# T15_PRI_SYS_V1_4.net
KiCad netlist of a schematic drawn in EAGLE
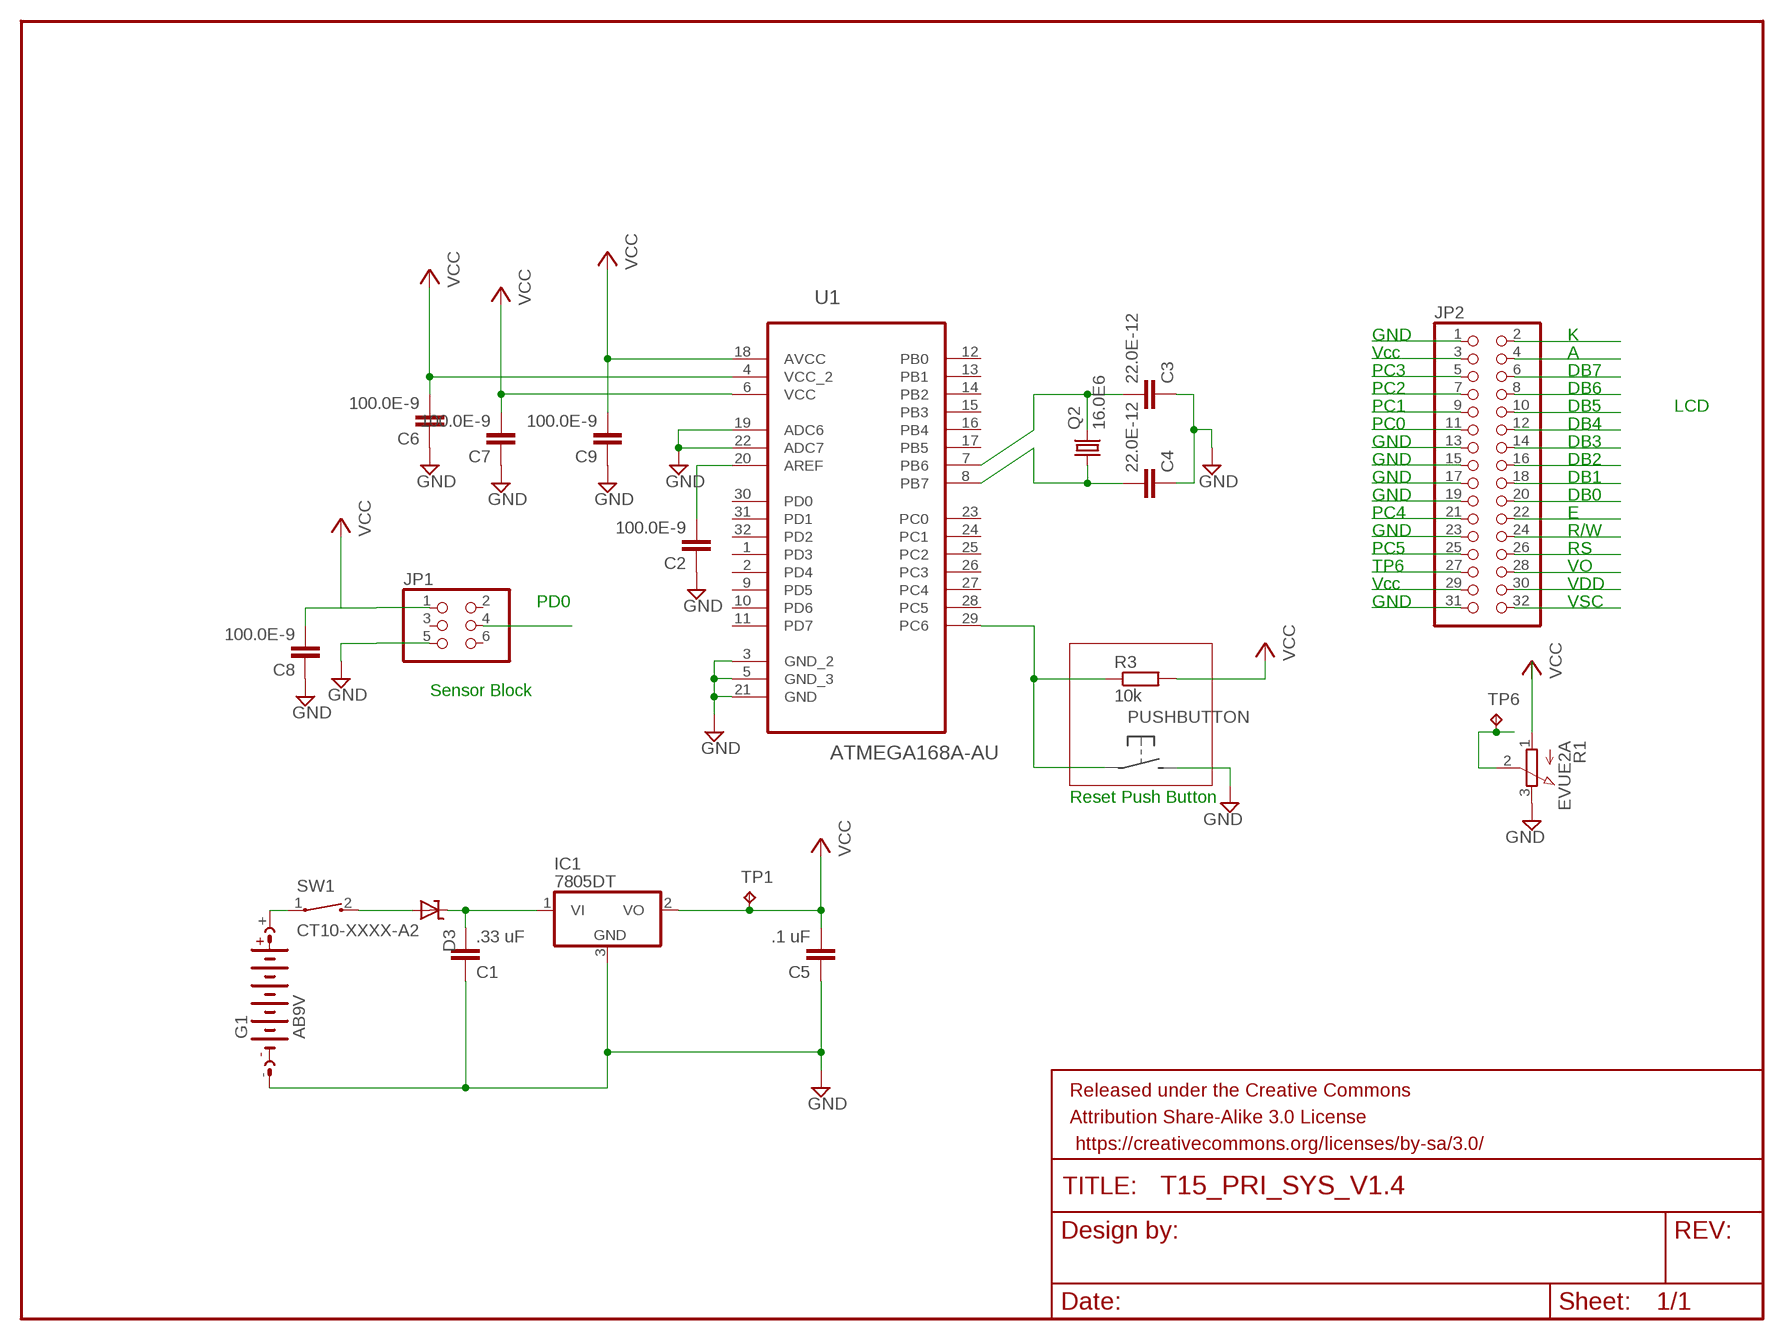
[diagram p0: schematic, sheet 1]

(export (version "E")
  (design (tool "Eeschema 10.0.6"))
  (components
    (comp (ref "C1")
      (value ".33 uF")
      (footprint "eagle-import:C025-024X044")
      (libsource (lib "eagle-import") (part "C-EU025-024X044"))
    )
    (comp (ref "C2")
      (value "100.0E-9")
      (footprint "eagle-import:C025-024X044")
      (libsource (lib "eagle-import") (part "C-EU025-024X044"))
    )
    (comp (ref "C3")
      (value "22.0E-12")
      (footprint "eagle-import:C025-024X044")
      (libsource (lib "eagle-import") (part "C-EU025-024X044"))
    )
    (comp (ref "C4")
      (value "22.0E-12")
      (footprint "eagle-import:C025-024X044")
      (libsource (lib "eagle-import") (part "C-EU025-024X044"))
    )
    (comp (ref "C5")
      (value ".1 uF")
      (footprint "eagle-import:C025-024X044")
      (libsource (lib "eagle-import") (part "C-EU025-024X044"))
    )
    (comp (ref "C6")
      (value "100.0E-9")
      (footprint "eagle-import:C025-024X044")
      (libsource (lib "eagle-import") (part "C-EU025-024X044"))
    )
    (comp (ref "C7")
      (value "100.0E-9")
      (footprint "eagle-import:C025-024X044")
      (libsource (lib "eagle-import") (part "C-EU025-024X044"))
    )
    (comp (ref "C8")
      (value "100.0E-9")
      (footprint "eagle-import:C025-024X044")
      (libsource (lib "eagle-import") (part "C-EU025-024X044"))
    )
    (comp (ref "C9")
      (value "100.0E-9")
      (footprint "eagle-import:C025-024X044")
      (libsource (lib "eagle-import") (part "C-EU025-024X044"))
    )
    (comp (ref "D3")
      (value "SUPPRESSOR-SMBJ")
      (footprint "eagle-import:SMBJ")
      (libsource (lib "eagle-import") (part "SUPPRESSOR-SMBJ"))
    )
    (comp (ref "FRAME1")
      (value "FRAME-LETTER")
      (footprint "eagle-import:CREATIVE_COMMONS")
      (libsource (lib "eagle-import") (part "FRAME-LETTER"))
    )
    (comp (ref "G1")
      (value "AB9V")
      (footprint "eagle-import:AB9V")
      (libsource (lib "eagle-import") (part "AB9V"))
    )
    (comp (ref "IC1")
      (value "7805DT")
      (footprint "eagle-import:TO252")
      (libsource (lib "eagle-import") (part "78DT05"))
    )
    (comp (ref "JP1")
      (value "PINHD-2X3/90")
      (footprint "eagle-import:2X03_90")
      (libsource (lib "eagle-import") (part "PINHD-2X3/90"))
    )
    (comp (ref "JP2")
      (value "PINHD-2X16")
      (footprint "eagle-import:2X16")
      (libsource (lib "eagle-import") (part "PINHD-2X16"))
    )
    (comp (ref "Q2")
      (value "16.0E6")
      (footprint "eagle-import:HC49_S")
      (libsource (lib "eagle-import") (part "CRYSTALHC49S"))
    )
    (comp (ref "R1")
      (value "EVUE2A")
      (footprint "eagle-import:EVUE")
      (libsource (lib "eagle-import") (part "EVUE2A"))
    )
    (comp (ref "R3")
      (value "10k")
      (footprint "eagle-import:0204_5")
      (libsource (lib "eagle-import") (part "R-EU_0204/5"))
    )
    (comp (ref "SW1")
      (value "CT10-XXXX-A2")
      (footprint "eagle-import:CT10-XXXX-A2")
      (libsource (lib "eagle-import") (part "CT10-XXXX-A2"))
    )
    (comp (ref "TP1")
      (value "TPB1,27")
      (footprint "eagle-import:B1,27")
      (libsource (lib "eagle-import") (part "TPB1,27"))
    )
    (comp (ref "TP6")
      (value "TPB1,27")
      (footprint "eagle-import:B1,27")
      (libsource (lib "eagle-import") (part "TPB1,27"))
    )
    (comp (ref "U1")
      (value "ATMEGA168A-AU")
      (footprint "eagle-import:QFP80P900X900X120-32N")
      (libsource (lib "eagle-import") (part "ATMEGA168A-AU"))
    )
  )
  (nets
    (net (code "1") (name "GND") (class "Default")
      (node (ref "C1") (pin "1") (pinfunction "1_1") (pintype "passive"))
      (node (ref "C2") (pin "1") (pinfunction "1_1") (pintype "passive"))
      (node (ref "C3") (pin "1") (pinfunction "1_1") (pintype "passive"))
      (node (ref "C4") (pin "1") (pinfunction "1_1") (pintype "passive"))
      (node (ref "C5") (pin "1") (pinfunction "1_1") (pintype "passive"))
      (node (ref "C6") (pin "1") (pinfunction "1_1") (pintype "passive"))
      (node (ref "C7") (pin "1") (pinfunction "1_1") (pintype "passive"))
      (node (ref "C8") (pin "1") (pinfunction "1_1") (pintype "passive"))
      (node (ref "C9") (pin "1") (pinfunction "1_1") (pintype "passive"))
      (node (ref "G1") (pin "-") (pinfunction "-_-") (pintype "passive"))
      (node (ref "IC1") (pin "3") (pinfunction "GND_3") (pintype "passive"))
      (node (ref "JP1") (pin "5") (pinfunction "5_5") (pintype "passive"))
      (node (ref "R1") (pin "3") (pinfunction "E_3") (pintype "passive"))
      (node (ref "U1") (pin "19") (pinfunction "ADC6_19") (pintype "input"))
      (node (ref "U1") (pin "21") (pinfunction "GND_21") (pintype "passive"))
      (node (ref "U1") (pin "22") (pinfunction "ADC7_22") (pintype "input"))
      (node (ref "U1") (pin "3") (pinfunction "GND_2_3") (pintype "passive"))
      (node (ref "U1") (pin "5") (pinfunction "GND_3_5") (pintype "passive"))
    )
    (net (code "2") (name "Net-(D3-PadA)") (class "Default")
      (node (ref "D3") (pin "A") (pinfunction "A_A") (pintype "passive"))
      (node (ref "SW1") (pin "2") (pinfunction "2_2") (pintype "passive"))
    )
    (net (code "3") (name "Net-(G1-Pad+)") (class "Default")
      (node (ref "G1") (pin "+") (pinfunction "+_+") (pintype "passive"))
      (node (ref "SW1") (pin "1") (pinfunction "1_1") (pintype "passive"))
    )
    (net (code "4") (name "Net-(IC1-VI)") (class "Default")
      (node (ref "C1") (pin "2") (pinfunction "2_2") (pintype "passive"))
      (node (ref "D3") (pin "C") (pinfunction "C_C") (pintype "passive"))
      (node (ref "IC1") (pin "1") (pinfunction "VI_1") (pintype "input"))
    )
    (net (code "5") (name "Net-(R1-S)") (class "Default")
      (node (ref "R1") (pin "2") (pinfunction "S_2") (pintype "passive"))
      (node (ref "TP6") (pin "TP") (pinfunction "TP_TP") (pintype "input"))
    )
    (net (code "6") (name "Net-(U1-AREF)") (class "Default")
      (node (ref "C2") (pin "2") (pinfunction "2_2") (pintype "passive"))
      (node (ref "U1") (pin "20") (pinfunction "AREF_20") (pintype "input"))
    )
    (net (code "7") (name "Net-(U1-PB6)") (class "Default")
      (node (ref "C3") (pin "2") (pinfunction "2_2") (pintype "passive"))
      (node (ref "Q2") (pin "2") (pinfunction "2_2") (pintype "passive"))
      (node (ref "U1") (pin "7") (pinfunction "PB6_7") (pintype "bidirectional"))
    )
    (net (code "8") (name "Net-(U1-PB7)") (class "Default")
      (node (ref "C4") (pin "2") (pinfunction "2_2") (pintype "passive"))
      (node (ref "Q2") (pin "1") (pinfunction "1_1") (pintype "passive"))
      (node (ref "U1") (pin "8") (pinfunction "PB7_8") (pintype "bidirectional"))
    )
    (net (code "9") (name "Net-(U1-PC6)") (class "Default")
      (node (ref "R3") (pin "1") (pinfunction "1_1") (pintype "passive"))
      (node (ref "U1") (pin "29") (pinfunction "PC6_29") (pintype "bidirectional"))
    )
    (net (code "10") (name "VCC") (class "Default")
      (node (ref "C5") (pin "2") (pinfunction "2_2") (pintype "passive"))
      (node (ref "C6") (pin "2") (pinfunction "2_2") (pintype "passive"))
      (node (ref "C7") (pin "2") (pinfunction "2_2") (pintype "passive"))
      (node (ref "C8") (pin "2") (pinfunction "2_2") (pintype "passive"))
      (node (ref "C9") (pin "2") (pinfunction "2_2") (pintype "passive"))
      (node (ref "IC1") (pin "2") (pinfunction "VO_2") (pintype "passive"))
      (node (ref "JP1") (pin "1") (pinfunction "1_1") (pintype "passive"))
      (node (ref "R3") (pin "2") (pinfunction "2_2") (pintype "passive"))
      (node (ref "TP1") (pin "TP") (pinfunction "TP_TP") (pintype "input"))
      (node (ref "U1") (pin "18") (pinfunction "AVCC_18") (pintype "power_in"))
      (node (ref "U1") (pin "4") (pinfunction "VCC_2_4") (pintype "power_in"))
      (node (ref "U1") (pin "6") (pinfunction "VCC_6") (pintype "power_in"))
    )
    (net (code "11") (name "unconnected-(JP1-Pad2)") (class "Default")
      (node (ref "JP1") (pin "2") (pinfunction "2_2") (pintype "passive"))
    )
    (net (code "12") (name "unconnected-(JP1-Pad3)") (class "Default")
      (node (ref "JP1") (pin "3") (pinfunction "3_3") (pintype "passive"))
    )
    (net (code "13") (name "unconnected-(JP1-Pad4)") (class "Default")
      (node (ref "JP1") (pin "4") (pinfunction "4_4") (pintype "passive"))
    )
    (net (code "14") (name "unconnected-(JP1-Pad6)") (class "Default")
      (node (ref "JP1") (pin "6") (pinfunction "6_6") (pintype "passive"))
    )
    (net (code "15") (name "unconnected-(JP2-Pad1)") (class "Default")
      (node (ref "JP2") (pin "1") (pinfunction "1_1") (pintype "passive"))
    )
    (net (code "16") (name "unconnected-(JP2-Pad2)") (class "Default")
      (node (ref "JP2") (pin "2") (pinfunction "2_2") (pintype "passive"))
    )
    (net (code "17") (name "unconnected-(JP2-Pad3)") (class "Default")
      (node (ref "JP2") (pin "3") (pinfunction "3_3") (pintype "passive"))
    )
    (net (code "18") (name "unconnected-(JP2-Pad4)") (class "Default")
      (node (ref "JP2") (pin "4") (pinfunction "4_4") (pintype "passive"))
    )
    (net (code "19") (name "unconnected-(JP2-Pad5)") (class "Default")
      (node (ref "JP2") (pin "5") (pinfunction "5_5") (pintype "passive"))
    )
    (net (code "20") (name "unconnected-(JP2-Pad6)") (class "Default")
      (node (ref "JP2") (pin "6") (pinfunction "6_6") (pintype "passive"))
    )
    (net (code "21") (name "unconnected-(JP2-Pad7)") (class "Default")
      (node (ref "JP2") (pin "7") (pinfunction "7_7") (pintype "passive"))
    )
    (net (code "22") (name "unconnected-(JP2-Pad8)") (class "Default")
      (node (ref "JP2") (pin "8") (pinfunction "8_8") (pintype "passive"))
    )
    (net (code "23") (name "unconnected-(JP2-Pad9)") (class "Default")
      (node (ref "JP2") (pin "9") (pinfunction "9_9") (pintype "passive"))
    )
    (net (code "24") (name "unconnected-(JP2-Pad10)") (class "Default")
      (node (ref "JP2") (pin "10") (pinfunction "10_10") (pintype "passive"))
    )
    (net (code "25") (name "unconnected-(JP2-Pad11)") (class "Default")
      (node (ref "JP2") (pin "11") (pinfunction "11_11") (pintype "passive"))
    )
    (net (code "26") (name "unconnected-(JP2-Pad12)") (class "Default")
      (node (ref "JP2") (pin "12") (pinfunction "12_12") (pintype "passive"))
    )
    (net (code "27") (name "unconnected-(JP2-Pad13)") (class "Default")
      (node (ref "JP2") (pin "13") (pinfunction "13_13") (pintype "passive"))
    )
    (net (code "28") (name "unconnected-(JP2-Pad14)") (class "Default")
      (node (ref "JP2") (pin "14") (pinfunction "14_14") (pintype "passive"))
    )
    (net (code "29") (name "unconnected-(JP2-Pad15)") (class "Default")
      (node (ref "JP2") (pin "15") (pinfunction "15_15") (pintype "passive"))
    )
    (net (code "30") (name "unconnected-(JP2-Pad16)") (class "Default")
      (node (ref "JP2") (pin "16") (pinfunction "16_16") (pintype "passive"))
    )
    (net (code "31") (name "unconnected-(JP2-Pad17)") (class "Default")
      (node (ref "JP2") (pin "17") (pinfunction "17_17") (pintype "passive"))
    )
    (net (code "32") (name "unconnected-(JP2-Pad18)") (class "Default")
      (node (ref "JP2") (pin "18") (pinfunction "18_18") (pintype "passive"))
    )
    (net (code "33") (name "unconnected-(JP2-Pad19)") (class "Default")
      (node (ref "JP2") (pin "19") (pinfunction "19_19") (pintype "passive"))
    )
    (net (code "34") (name "unconnected-(JP2-Pad20)") (class "Default")
      (node (ref "JP2") (pin "20") (pinfunction "20_20") (pintype "passive"))
    )
    (net (code "35") (name "unconnected-(JP2-Pad21)") (class "Default")
      (node (ref "JP2") (pin "21") (pinfunction "21_21") (pintype "passive"))
    )
    (net (code "36") (name "unconnected-(JP2-Pad22)") (class "Default")
      (node (ref "JP2") (pin "22") (pinfunction "22_22") (pintype "passive"))
    )
    (net (code "37") (name "unconnected-(JP2-Pad23)") (class "Default")
      (node (ref "JP2") (pin "23") (pinfunction "23_23") (pintype "passive"))
    )
    (net (code "38") (name "unconnected-(JP2-Pad24)") (class "Default")
      (node (ref "JP2") (pin "24") (pinfunction "24_24") (pintype "passive"))
    )
    (net (code "39") (name "unconnected-(JP2-Pad25)") (class "Default")
      (node (ref "JP2") (pin "25") (pinfunction "25_25") (pintype "passive"))
    )
    (net (code "40") (name "unconnected-(JP2-Pad26)") (class "Default")
      (node (ref "JP2") (pin "26") (pinfunction "26_26") (pintype "passive"))
    )
    (net (code "41") (name "unconnected-(JP2-Pad27)") (class "Default")
      (node (ref "JP2") (pin "27") (pinfunction "27_27") (pintype "passive"))
    )
    (net (code "42") (name "unconnected-(JP2-Pad28)") (class "Default")
      (node (ref "JP2") (pin "28") (pinfunction "28_28") (pintype "passive"))
    )
    (net (code "43") (name "unconnected-(JP2-Pad29)") (class "Default")
      (node (ref "JP2") (pin "29") (pinfunction "29_29") (pintype "passive"))
    )
    (net (code "44") (name "unconnected-(JP2-Pad30)") (class "Default")
      (node (ref "JP2") (pin "30") (pinfunction "30_30") (pintype "passive"))
    )
    (net (code "45") (name "unconnected-(JP2-Pad31)") (class "Default")
      (node (ref "JP2") (pin "31") (pinfunction "31_31") (pintype "passive"))
    )
    (net (code "46") (name "unconnected-(JP2-Pad32)") (class "Default")
      (node (ref "JP2") (pin "32") (pinfunction "32_32") (pintype "passive"))
    )
    (net (code "47") (name "unconnected-(R1-A-Pad1)") (class "Default")
      (node (ref "R1") (pin "1") (pinfunction "A_1") (pintype "passive"))
    )
    (net (code "48") (name "unconnected-(U1-PB0-Pad12)") (class "Default")
      (node (ref "U1") (pin "12") (pinfunction "PB0_12") (pintype "bidirectional"))
    )
    (net (code "49") (name "unconnected-(U1-PB1-Pad13)") (class "Default")
      (node (ref "U1") (pin "13") (pinfunction "PB1_13") (pintype "bidirectional"))
    )
    (net (code "50") (name "unconnected-(U1-PB2-Pad14)") (class "Default")
      (node (ref "U1") (pin "14") (pinfunction "PB2_14") (pintype "bidirectional"))
    )
    (net (code "51") (name "unconnected-(U1-PB3-Pad15)") (class "Default")
      (node (ref "U1") (pin "15") (pinfunction "PB3_15") (pintype "bidirectional"))
    )
    (net (code "52") (name "unconnected-(U1-PB4-Pad16)") (class "Default")
      (node (ref "U1") (pin "16") (pinfunction "PB4_16") (pintype "bidirectional"))
    )
    (net (code "53") (name "unconnected-(U1-PB5-Pad17)") (class "Default")
      (node (ref "U1") (pin "17") (pinfunction "PB5_17") (pintype "bidirectional"))
    )
    (net (code "54") (name "unconnected-(U1-PC0-Pad23)") (class "Default")
      (node (ref "U1") (pin "23") (pinfunction "PC0_23") (pintype "bidirectional"))
    )
    (net (code "55") (name "unconnected-(U1-PC1-Pad24)") (class "Default")
      (node (ref "U1") (pin "24") (pinfunction "PC1_24") (pintype "bidirectional"))
    )
    (net (code "56") (name "unconnected-(U1-PC2-Pad25)") (class "Default")
      (node (ref "U1") (pin "25") (pinfunction "PC2_25") (pintype "bidirectional"))
    )
    (net (code "57") (name "unconnected-(U1-PC3-Pad26)") (class "Default")
      (node (ref "U1") (pin "26") (pinfunction "PC3_26") (pintype "bidirectional"))
    )
    (net (code "58") (name "unconnected-(U1-PC4-Pad27)") (class "Default")
      (node (ref "U1") (pin "27") (pinfunction "PC4_27") (pintype "bidirectional"))
    )
    (net (code "59") (name "unconnected-(U1-PC5-Pad28)") (class "Default")
      (node (ref "U1") (pin "28") (pinfunction "PC5_28") (pintype "bidirectional"))
    )
    (net (code "60") (name "unconnected-(U1-PD0-Pad30)") (class "Default")
      (node (ref "U1") (pin "30") (pinfunction "PD0_30") (pintype "bidirectional"))
    )
    (net (code "61") (name "unconnected-(U1-PD1-Pad31)") (class "Default")
      (node (ref "U1") (pin "31") (pinfunction "PD1_31") (pintype "bidirectional"))
    )
    (net (code "62") (name "unconnected-(U1-PD2-Pad32)") (class "Default")
      (node (ref "U1") (pin "32") (pinfunction "PD2_32") (pintype "bidirectional"))
    )
    (net (code "63") (name "unconnected-(U1-PD3-Pad1)") (class "Default")
      (node (ref "U1") (pin "1") (pinfunction "PD3_1") (pintype "bidirectional"))
    )
    (net (code "64") (name "unconnected-(U1-PD4-Pad2)") (class "Default")
      (node (ref "U1") (pin "2") (pinfunction "PD4_2") (pintype "bidirectional"))
    )
    (net (code "65") (name "unconnected-(U1-PD5-Pad9)") (class "Default")
      (node (ref "U1") (pin "9") (pinfunction "PD5_9") (pintype "bidirectional"))
    )
    (net (code "66") (name "unconnected-(U1-PD6-Pad10)") (class "Default")
      (node (ref "U1") (pin "10") (pinfunction "PD6_10") (pintype "bidirectional"))
    )
    (net (code "67") (name "unconnected-(U1-PD7-Pad11)") (class "Default")
      (node (ref "U1") (pin "11") (pinfunction "PD7_11") (pintype "bidirectional"))
    )
  )
)
